# Sheet.net
KiCad netlist of a schematic drawn in Altium Designer
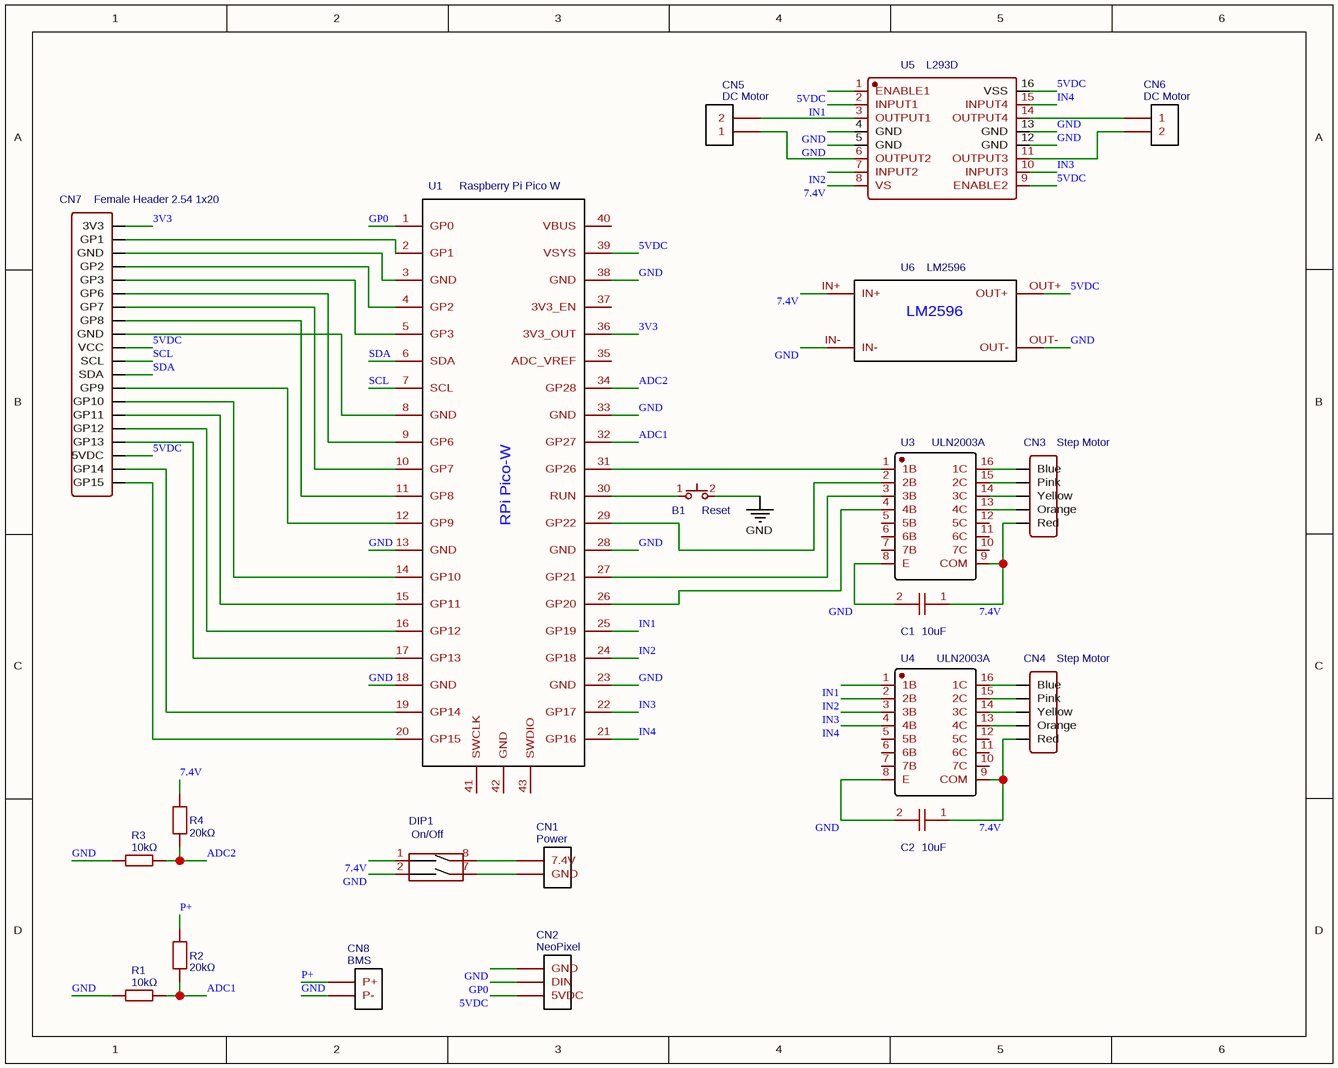
[diagram p0: Sheet.schdoc]

(export (version "E")
  (design (tool "Eeschema 10.0.6"))
  (components
    (comp (ref "B1")
      (value "Reset")
      (fields (field (name "CONTRIBUTOR") "Zayden"))
      (libsource (lib "altium-import") (part "root_0_Reset_"))
    )
    (comp (ref "C1")
      (value "10uF")
      (fields
        (field (name "BOM_SUPPLIER PART") "C3695070")
        (field (name "BOM_MANUFACTURER PART") "FG26X7R1E106KRT00")
        (field (name "CONTRIBUTOR") "lcsc")
      )
      (libsource (lib "altium-import") (part "root_2_10uF_"))
    )
    (comp (ref "C2")
      (value "10uF")
      (fields
        (field (name "BOM_SUPPLIER PART") "C3695070")
        (field (name "BOM_MANUFACTURER PART") "FG26X7R1E106KRT00")
        (field (name "CONTRIBUTOR") "lcsc")
      )
      (libsource (lib "altium-import") (part "root_2_10uF_"))
    )
    (comp (ref "CN1")
      (value "Power")
      (fields (field (name "BOM_MANUFACTURER PART") "JST") (field (name "CONTRIBUTOR") "amun"))
      (libsource (lib "altium-import") (part "root_0_Power_"))
    )
    (comp (ref "CN2")
      (value "NeoPixel")
      (fields (field (name "BOM_MANUFACTURER PART") "JST") (field (name "CONTRIBUTOR") "amun"))
      (libsource (lib "altium-import") (part "root_0_NeoPixel_"))
    )
    (comp (ref "CN3")
      (value "Step Motor")
      (fields (field (name "CONTRIBUTOR") "PuranSingh"))
      (libsource (lib "altium-import") (part "root_0_Step Motor_"))
    )
    (comp (ref "CN4")
      (value "Step Motor")
      (fields (field (name "CONTRIBUTOR") "PuranSingh"))
      (libsource (lib "altium-import") (part "root_0_Step Motor_"))
    )
    (comp (ref "CN5")
      (value "DC Motor")
      (fields (field (name "BOM_MANUFACTURER PART") "JST") (field (name "CONTRIBUTOR") "amun"))
      (libsource (lib "altium-import") (part "root_2_DC Motor_"))
    )
    (comp (ref "CN6")
      (value "DC Motor")
      (fields (field (name "BOM_MANUFACTURER PART") "JST") (field (name "CONTRIBUTOR") "amun"))
      (libsource (lib "altium-import") (part "root_0_DC Motor_"))
    )
    (comp (ref "CN7")
      (value "Female Header 2.54 1x20")
      (fields
        (field (name "BOM_MANUFACTURER PART") "2.54-1*20P母")
        (field (name "BOM_SUPPLIER PART") "C50984")
      )
      (libsource (lib "altium-import") (part "root_2_Female Header 2.54 1x20_"))
    )
    (comp (ref "CN8")
      (value "BMS")
      (fields (field (name "BOM_MANUFACTURER PART") "JST") (field (name "CONTRIBUTOR") "amun"))
      (libsource (lib "altium-import") (part "root_0_BMS_"))
    )
    (comp (ref "DIP1")
      (value "On/Off")
      (fields
        (field (name "BOM_MANUFACTURER PART") "DIP switchEI-08")
        (field (name "BOM_SUPPLIER PART") "C90019")
        (field (name "CONTRIBUTOR") "michalsky")
      )
      (libsource (lib "altium-import") (part "root_0_On/Off_"))
    )
    (comp (ref "R1")
      (value "10kΩ")
      (fields
        (field (name "BOM_SUPPLIER PART") "C136549")
        (field (name "BOM_MANUFACTURER PART") "RI40-1/4W-10KΩ ±5% T")
        (field (name "CONTRIBUTOR") "LCSC")
      )
      (libsource (lib "altium-import") (part "root_0_10kΩ_"))
    )
    (comp (ref "R2")
      (value "20kΩ")
      (fields
        (field (name "BOM_SUPPLIER PART") "C714021")
        (field (name "BOM_MANUFACTURER PART") "MF1/4W-20KΩ±1%T52")
        (field (name "CONTRIBUTOR") "LCSC")
      )
      (libsource (lib "altium-import") (part "root_1_20kΩ_"))
    )
    (comp (ref "R3")
      (value "10kΩ")
      (fields
        (field (name "BOM_SUPPLIER PART") "C136549")
        (field (name "BOM_MANUFACTURER PART") "RI40-1/4W-10KΩ ±5% T")
        (field (name "CONTRIBUTOR") "LCSC")
      )
      (libsource (lib "altium-import") (part "root_0_10kΩ_"))
    )
    (comp (ref "R4")
      (value "20kΩ")
      (fields
        (field (name "BOM_SUPPLIER PART") "C714021")
        (field (name "BOM_MANUFACTURER PART") "MF1/4W-20KΩ±1%T52")
        (field (name "CONTRIBUTOR") "LCSC")
      )
      (libsource (lib "altium-import") (part "root_1_20kΩ_"))
    )
    (comp (ref "U1")
      (value "Raspberry Pi Pico W")
      (fields
        (field (name "BOM_MANUFACTURER PART") "Pi Pico")
        (field (name "BOM_SUPPLIER PART") "Raspberry Pi Pico-W")
        (field (name "CONTRIBUTOR") "Rovonius")
      )
      (libsource (lib "altium-import") (part "root_0_Raspberry Pi Pico W_"))
    )
    (comp (ref "U3")
      (value "ULN2003A")
      (fields (field (name "BOM_MANUFACTURER PART") "ULN2003APG") (field (name "BOM_SUPPLIER PART") "C5251"))
      (libsource (lib "altium-import") (part "root_0_ULN2003A_"))
    )
    (comp (ref "U4")
      (value "ULN2003A")
      (fields (field (name "BOM_MANUFACTURER PART") "ULN2003APG") (field (name "BOM_SUPPLIER PART") "C5251"))
      (libsource (lib "altium-import") (part "root_0_ULN2003A_"))
    )
    (comp (ref "U5")
      (value "L293D")
      (fields
        (field (name "BOM_SUPPLIER PART") "C434590")
        (field (name "BOM_MANUFACTURER PART") "L293DN")
        (field (name "CONTRIBUTOR") "LCSC")
      )
      (libsource (lib "altium-import") (part "root_0_L293D_"))
    )
    (comp (ref "U6")
      (value "LM2596")
      (fields (field (name "CONTRIBUTOR") "Saad_Mazumder"))
      (libsource (lib "altium-import") (part "root_0_LM2596_"))
    )
  )
  (nets
    (net (code "1") (name "/3V3") (class "Default")
      (node (ref "CN7") (pin "20") (pinfunction "3V3_20") (pintype "passive"))
      (node (ref "U1") (pin "36") (pinfunction "3V3_OUT_36") (pintype "passive"))
    )
    (net (code "2") (name "/5VDC") (class "Default")
      (node (ref "CN2") (pin "3") (pinfunction "5VDC_3") (pintype "passive"))
      (node (ref "CN7") (pin "11") (pinfunction "VCC_11") (pintype "passive"))
      (node (ref "CN7") (pin "3") (pinfunction "5VDC_3") (pintype "passive"))
      (node (ref "U1") (pin "39") (pinfunction "VSYS_39") (pintype "passive"))
      (node (ref "U5") (pin "1") (pinfunction "ENABLE1_1") (pintype "passive"))
      (node (ref "U5") (pin "16") (pinfunction "VSS_16") (pintype "passive"))
      (node (ref "U5") (pin "9") (pinfunction "ENABLE2_9") (pintype "passive"))
      (node (ref "U6") (pin "OUT+") (pinfunction "OUT+_OUT+") (pintype "passive"))
    )
    (net (code "3") (name "/7.4V") (class "Default")
      (node (ref "C1") (pin "1") (pinfunction "1_1") (pintype "passive"))
      (node (ref "C2") (pin "1") (pinfunction "1_1") (pintype "passive"))
      (node (ref "CN3") (pin "1") (pinfunction "Red_1") (pintype "passive"))
      (node (ref "CN4") (pin "1") (pinfunction "Red_1") (pintype "passive"))
      (node (ref "DIP1") (pin "1") (pinfunction "1_1") (pintype "passive"))
      (node (ref "R4") (pin "2") (pinfunction "2_2") (pintype "passive"))
      (node (ref "U3") (pin "9") (pinfunction "COM_9") (pintype "passive"))
      (node (ref "U4") (pin "9") (pinfunction "COM_9") (pintype "passive"))
      (node (ref "U5") (pin "8") (pinfunction "VS_8") (pintype "passive"))
      (node (ref "U6") (pin "IN+") (pinfunction "IN+_IN+") (pintype "passive"))
    )
    (net (code "4") (name "/ADC1") (class "Default")
      (node (ref "R1") (pin "2") (pinfunction "2_2") (pintype "passive"))
      (node (ref "R2") (pin "1") (pinfunction "1_1") (pintype "passive"))
      (node (ref "U1") (pin "32") (pinfunction "GP27_32") (pintype "passive"))
    )
    (net (code "5") (name "/ADC2") (class "Default")
      (node (ref "R3") (pin "2") (pinfunction "2_2") (pintype "passive"))
      (node (ref "R4") (pin "1") (pinfunction "1_1") (pintype "passive"))
      (node (ref "U1") (pin "34") (pinfunction "GP28_34") (pintype "passive"))
    )
    (net (code "6") (name "/GP0") (class "Default")
      (node (ref "CN2") (pin "2") (pinfunction "DIN_2") (pintype "passive"))
      (node (ref "U1") (pin "1") (pinfunction "GP0_1") (pintype "passive"))
    )
    (net (code "7") (name "/IN1") (class "Default")
      (node (ref "U1") (pin "25") (pinfunction "GP19_25") (pintype "passive"))
      (node (ref "U4") (pin "1") (pinfunction "1B_1") (pintype "passive"))
      (node (ref "U5") (pin "2") (pinfunction "INPUT1_2") (pintype "passive"))
    )
    (net (code "8") (name "/IN2") (class "Default")
      (node (ref "U1") (pin "24") (pinfunction "GP18_24") (pintype "passive"))
      (node (ref "U4") (pin "2") (pinfunction "2B_2") (pintype "passive"))
      (node (ref "U5") (pin "7") (pinfunction "INPUT2_7") (pintype "passive"))
    )
    (net (code "9") (name "/IN3") (class "Default")
      (node (ref "U1") (pin "22") (pinfunction "GP17_22") (pintype "passive"))
      (node (ref "U4") (pin "3") (pinfunction "3B_3") (pintype "passive"))
      (node (ref "U5") (pin "10") (pinfunction "INPUT3_10") (pintype "passive"))
    )
    (net (code "10") (name "/IN4") (class "Default")
      (node (ref "U1") (pin "21") (pinfunction "GP16_21") (pintype "passive"))
      (node (ref "U4") (pin "4") (pinfunction "4B_4") (pintype "passive"))
      (node (ref "U5") (pin "15") (pinfunction "INPUT4_15") (pintype "passive"))
    )
    (net (code "11") (name "/P+") (class "Default")
      (node (ref "CN8") (pin "1") (pinfunction "P+_1") (pintype "passive"))
      (node (ref "R2") (pin "2") (pinfunction "2_2") (pintype "passive"))
    )
    (net (code "12") (name "/SCL") (class "Default")
      (node (ref "CN7") (pin "10") (pinfunction "SCL_10") (pintype "passive"))
      (node (ref "U1") (pin "7") (pinfunction "SCL_7") (pintype "passive"))
    )
    (net (code "13") (name "/SDA") (class "Default")
      (node (ref "CN7") (pin "9") (pinfunction "SDA_9") (pintype "passive"))
      (node (ref "U1") (pin "6") (pinfunction "SDA_6") (pintype "passive"))
    )
    (net (code "14") (name "GND") (class "Default")
      (node (ref "B1") (pin "2") (pinfunction "2_2") (pintype "passive"))
      (node (ref "C1") (pin "2") (pinfunction "2_2") (pintype "passive"))
      (node (ref "C2") (pin "2") (pinfunction "2_2") (pintype "passive"))
      (node (ref "CN2") (pin "1") (pinfunction "GND_1") (pintype "passive"))
      (node (ref "CN8") (pin "2") (pinfunction "P-_2") (pintype "passive"))
      (node (ref "DIP1") (pin "2") (pinfunction "2_2") (pintype "passive"))
      (node (ref "R1") (pin "1") (pinfunction "1_1") (pintype "passive"))
      (node (ref "R3") (pin "1") (pinfunction "1_1") (pintype "passive"))
      (node (ref "U1") (pin "13") (pinfunction "GND_13") (pintype "passive"))
      (node (ref "U1") (pin "18") (pinfunction "GND_18") (pintype "passive"))
      (node (ref "U1") (pin "23") (pinfunction "GND_23") (pintype "passive"))
      (node (ref "U1") (pin "28") (pinfunction "GND_28") (pintype "passive"))
      (node (ref "U1") (pin "33") (pinfunction "GND_33") (pintype "passive"))
      (node (ref "U1") (pin "38") (pinfunction "GND_38") (pintype "passive"))
      (node (ref "U3") (pin "8") (pinfunction "E_8") (pintype "passive"))
      (node (ref "U4") (pin "8") (pinfunction "E_8") (pintype "passive"))
      (node (ref "U5") (pin "12") (pinfunction "GND_12") (pintype "passive"))
      (node (ref "U5") (pin "13") (pinfunction "GND_13") (pintype "passive"))
      (node (ref "U5") (pin "4") (pinfunction "GND_4") (pintype "passive"))
      (node (ref "U5") (pin "5") (pinfunction "GND_5") (pintype "passive"))
      (node (ref "U6") (pin "IN-") (pinfunction "IN-_IN-") (pintype "passive"))
      (node (ref "U6") (pin "OUT-") (pinfunction "OUT-_OUT-") (pintype "passive"))
    )
    (net (code "15") (name "Net-(CN1-7.4V)") (class "Default")
      (node (ref "CN1") (pin "1") (pinfunction "7.4V_1") (pintype "passive"))
      (node (ref "DIP1") (pin "8") (pinfunction "8_8") (pintype "passive"))
    )
    (net (code "16") (name "Net-(CN1-GND)") (class "Default")
      (node (ref "CN1") (pin "2") (pinfunction "GND_2") (pintype "passive"))
      (node (ref "DIP1") (pin "7") (pinfunction "7_7") (pintype "passive"))
    )
    (net (code "17") (name "Net-(CN3-Blue)") (class "Default")
      (node (ref "CN3") (pin "5") (pinfunction "Blue_5") (pintype "passive"))
      (node (ref "U3") (pin "16") (pinfunction "1C_16") (pintype "passive"))
    )
    (net (code "18") (name "Net-(CN3-Orange)") (class "Default")
      (node (ref "CN3") (pin "2") (pinfunction "Orange_2") (pintype "passive"))
      (node (ref "U3") (pin "13") (pinfunction "4C_13") (pintype "passive"))
    )
    (net (code "19") (name "Net-(CN3-Pink)") (class "Default")
      (node (ref "CN3") (pin "4") (pinfunction "Pink_4") (pintype "passive"))
      (node (ref "U3") (pin "15") (pinfunction "2C_15") (pintype "passive"))
    )
    (net (code "20") (name "Net-(CN3-Yellow)") (class "Default")
      (node (ref "CN3") (pin "3") (pinfunction "Yellow_3") (pintype "passive"))
      (node (ref "U3") (pin "14") (pinfunction "3C_14") (pintype "passive"))
    )
    (net (code "21") (name "Net-(CN4-Blue)") (class "Default")
      (node (ref "CN4") (pin "5") (pinfunction "Blue_5") (pintype "passive"))
      (node (ref "U4") (pin "16") (pinfunction "1C_16") (pintype "passive"))
    )
    (net (code "22") (name "Net-(CN4-Orange)") (class "Default")
      (node (ref "CN4") (pin "2") (pinfunction "Orange_2") (pintype "passive"))
      (node (ref "U4") (pin "13") (pinfunction "4C_13") (pintype "passive"))
    )
    (net (code "23") (name "Net-(CN4-Pink)") (class "Default")
      (node (ref "CN4") (pin "4") (pinfunction "Pink_4") (pintype "passive"))
      (node (ref "U4") (pin "15") (pinfunction "2C_15") (pintype "passive"))
    )
    (net (code "24") (name "Net-(CN4-Yellow)") (class "Default")
      (node (ref "CN4") (pin "3") (pinfunction "Yellow_3") (pintype "passive"))
      (node (ref "U4") (pin "14") (pinfunction "3C_14") (pintype "passive"))
    )
    (net (code "25") (name "Net-(CN7-GND-Pad12)") (class "Default")
      (node (ref "CN7") (pin "12") (pinfunction "GND_12") (pintype "passive"))
      (node (ref "U1") (pin "8") (pinfunction "GND_8") (pintype "passive"))
    )
    (net (code "26") (name "Net-(CN7-GND-Pad18)") (class "Default")
      (node (ref "CN7") (pin "18") (pinfunction "GND_18") (pintype "passive"))
      (node (ref "U1") (pin "3") (pinfunction "GND_3") (pintype "passive"))
    )
    (net (code "27") (name "Net-(CN7-GP1)") (class "Default")
      (node (ref "CN7") (pin "19") (pinfunction "GP1_19") (pintype "passive"))
      (node (ref "U1") (pin "2") (pinfunction "GP1_2") (pintype "passive"))
    )
    (net (code "28") (name "Net-(CN7-GP2)") (class "Default")
      (node (ref "CN7") (pin "17") (pinfunction "GP2_17") (pintype "passive"))
      (node (ref "U1") (pin "4") (pinfunction "GP2_4") (pintype "passive"))
    )
    (net (code "29") (name "Net-(CN7-GP3)") (class "Default")
      (node (ref "CN7") (pin "16") (pinfunction "GP3_16") (pintype "passive"))
      (node (ref "U1") (pin "5") (pinfunction "GP3_5") (pintype "passive"))
    )
    (net (code "30") (name "Net-(CN7-GP6)") (class "Default")
      (node (ref "CN7") (pin "15") (pinfunction "GP6_15") (pintype "passive"))
      (node (ref "U1") (pin "9") (pinfunction "GP6_9") (pintype "passive"))
    )
    (net (code "31") (name "Net-(CN7-GP7)") (class "Default")
      (node (ref "CN7") (pin "14") (pinfunction "GP7_14") (pintype "passive"))
      (node (ref "U1") (pin "10") (pinfunction "GP7_10") (pintype "passive"))
    )
    (net (code "32") (name "Net-(CN7-GP8)") (class "Default")
      (node (ref "CN7") (pin "13") (pinfunction "GP8_13") (pintype "passive"))
      (node (ref "U1") (pin "11") (pinfunction "GP8_11") (pintype "passive"))
    )
    (net (code "33") (name "Net-(CN7-GP9)") (class "Default")
      (node (ref "CN7") (pin "8") (pinfunction "GP9_8") (pintype "passive"))
      (node (ref "U1") (pin "12") (pinfunction "GP9_12") (pintype "passive"))
    )
    (net (code "34") (name "Net-(CN7-GP10)") (class "Default")
      (node (ref "CN7") (pin "7") (pinfunction "GP10_7") (pintype "passive"))
      (node (ref "U1") (pin "14") (pinfunction "GP10_14") (pintype "passive"))
    )
    (net (code "35") (name "Net-(CN7-GP11)") (class "Default")
      (node (ref "CN7") (pin "6") (pinfunction "GP11_6") (pintype "passive"))
      (node (ref "U1") (pin "15") (pinfunction "GP11_15") (pintype "passive"))
    )
    (net (code "36") (name "Net-(CN7-GP12)") (class "Default")
      (node (ref "CN7") (pin "5") (pinfunction "GP12_5") (pintype "passive"))
      (node (ref "U1") (pin "16") (pinfunction "GP12_16") (pintype "passive"))
    )
    (net (code "37") (name "Net-(CN7-GP13)") (class "Default")
      (node (ref "CN7") (pin "4") (pinfunction "GP13_4") (pintype "passive"))
      (node (ref "U1") (pin "17") (pinfunction "GP13_17") (pintype "passive"))
    )
    (net (code "38") (name "Net-(CN7-GP14)") (class "Default")
      (node (ref "CN7") (pin "2") (pinfunction "GP14_2") (pintype "passive"))
      (node (ref "U1") (pin "19") (pinfunction "GP14_19") (pintype "passive"))
    )
    (net (code "39") (name "Net-(CN7-GP15)") (class "Default")
      (node (ref "CN7") (pin "1") (pinfunction "GP15_1") (pintype "passive"))
      (node (ref "U1") (pin "20") (pinfunction "GP15_20") (pintype "passive"))
    )
    (net (code "40") (name "Net-(U1-GP20)") (class "Default")
      (node (ref "U1") (pin "26") (pinfunction "GP20_26") (pintype "passive"))
      (node (ref "U3") (pin "4") (pinfunction "4B_4") (pintype "passive"))
    )
    (net (code "41") (name "Net-(U1-GP21)") (class "Default")
      (node (ref "U1") (pin "27") (pinfunction "GP21_27") (pintype "passive"))
      (node (ref "U3") (pin "3") (pinfunction "3B_3") (pintype "passive"))
    )
    (net (code "42") (name "Net-(U1-GP22)") (class "Default")
      (node (ref "U1") (pin "29") (pinfunction "GP22_29") (pintype "passive"))
      (node (ref "U3") (pin "2") (pinfunction "2B_2") (pintype "passive"))
    )
    (net (code "43") (name "Net-(U1-GP26)") (class "Default")
      (node (ref "U1") (pin "31") (pinfunction "GP26_31") (pintype "passive"))
      (node (ref "U3") (pin "1") (pinfunction "1B_1") (pintype "passive"))
    )
    (net (code "44") (name "Net-(U1-RUN)") (class "Default")
      (node (ref "B1") (pin "1") (pinfunction "1_1") (pintype "passive"))
      (node (ref "U1") (pin "30") (pinfunction "RUN_30") (pintype "passive"))
    )
    (net (code "45") (name "Net-(U5-OUTPUT1)") (class "Default")
      (node (ref "CN5") (pin "2") (pinfunction "2_2") (pintype "passive"))
      (node (ref "U5") (pin "3") (pinfunction "OUTPUT1_3") (pintype "passive"))
    )
    (net (code "46") (name "Net-(U5-OUTPUT2)") (class "Default")
      (node (ref "CN5") (pin "1") (pinfunction "1_1") (pintype "passive"))
      (node (ref "U5") (pin "6") (pinfunction "OUTPUT2_6") (pintype "passive"))
    )
    (net (code "47") (name "Net-(U5-OUTPUT3)") (class "Default")
      (node (ref "CN6") (pin "2") (pinfunction "2_2") (pintype "passive"))
      (node (ref "U5") (pin "11") (pinfunction "OUTPUT3_11") (pintype "passive"))
    )
    (net (code "48") (name "Net-(U5-OUTPUT4)") (class "Default")
      (node (ref "CN6") (pin "1") (pinfunction "1_1") (pintype "passive"))
      (node (ref "U5") (pin "14") (pinfunction "OUTPUT4_14") (pintype "passive"))
    )
    (net (code "49") (name "unconnected-(U1-3V3_EN-Pad37)") (class "Default")
      (node (ref "U1") (pin "37") (pinfunction "3V3_EN_37") (pintype "passive"))
    )
    (net (code "50") (name "unconnected-(U1-ADC_VREF-Pad35)") (class "Default")
      (node (ref "U1") (pin "35") (pinfunction "ADC_VREF_35") (pintype "passive"))
    )
    (net (code "51") (name "unconnected-(U1-GND-Pad42)") (class "Default")
      (node (ref "U1") (pin "42") (pinfunction "GND_42") (pintype "passive"))
    )
    (net (code "52") (name "unconnected-(U1-SWCLK-Pad41)") (class "Default")
      (node (ref "U1") (pin "41") (pinfunction "SWCLK_41") (pintype "passive"))
    )
    (net (code "53") (name "unconnected-(U1-SWDIO-Pad43)") (class "Default")
      (node (ref "U1") (pin "43") (pinfunction "SWDIO_43") (pintype "passive"))
    )
    (net (code "54") (name "unconnected-(U1-VBUS-Pad40)") (class "Default")
      (node (ref "U1") (pin "40") (pinfunction "VBUS_40") (pintype "passive"))
    )
    (net (code "55") (name "unconnected-(U3-5B-Pad5)") (class "Default")
      (node (ref "U3") (pin "5") (pinfunction "5B_5") (pintype "passive"))
    )
    (net (code "56") (name "unconnected-(U3-5C-Pad12)") (class "Default")
      (node (ref "U3") (pin "12") (pinfunction "5C_12") (pintype "passive"))
    )
    (net (code "57") (name "unconnected-(U3-6B-Pad6)") (class "Default")
      (node (ref "U3") (pin "6") (pinfunction "6B_6") (pintype "passive"))
    )
    (net (code "58") (name "unconnected-(U3-6C-Pad11)") (class "Default")
      (node (ref "U3") (pin "11") (pinfunction "6C_11") (pintype "passive"))
    )
    (net (code "59") (name "unconnected-(U3-7B-Pad7)") (class "Default")
      (node (ref "U3") (pin "7") (pinfunction "7B_7") (pintype "passive"))
    )
    (net (code "60") (name "unconnected-(U3-7C-Pad10)") (class "Default")
      (node (ref "U3") (pin "10") (pinfunction "7C_10") (pintype "passive"))
    )
    (net (code "61") (name "unconnected-(U4-5B-Pad5)") (class "Default")
      (node (ref "U4") (pin "5") (pinfunction "5B_5") (pintype "passive"))
    )
    (net (code "62") (name "unconnected-(U4-5C-Pad12)") (class "Default")
      (node (ref "U4") (pin "12") (pinfunction "5C_12") (pintype "passive"))
    )
    (net (code "63") (name "unconnected-(U4-6B-Pad6)") (class "Default")
      (node (ref "U4") (pin "6") (pinfunction "6B_6") (pintype "passive"))
    )
    (net (code "64") (name "unconnected-(U4-6C-Pad11)") (class "Default")
      (node (ref "U4") (pin "11") (pinfunction "6C_11") (pintype "passive"))
    )
    (net (code "65") (name "unconnected-(U4-7B-Pad7)") (class "Default")
      (node (ref "U4") (pin "7") (pinfunction "7B_7") (pintype "passive"))
    )
    (net (code "66") (name "unconnected-(U4-7C-Pad10)") (class "Default")
      (node (ref "U4") (pin "10") (pinfunction "7C_10") (pintype "passive"))
    )
  )
)
